# 01_MCU.net
KiCad netlist of a schematic drawn in Altium Designer
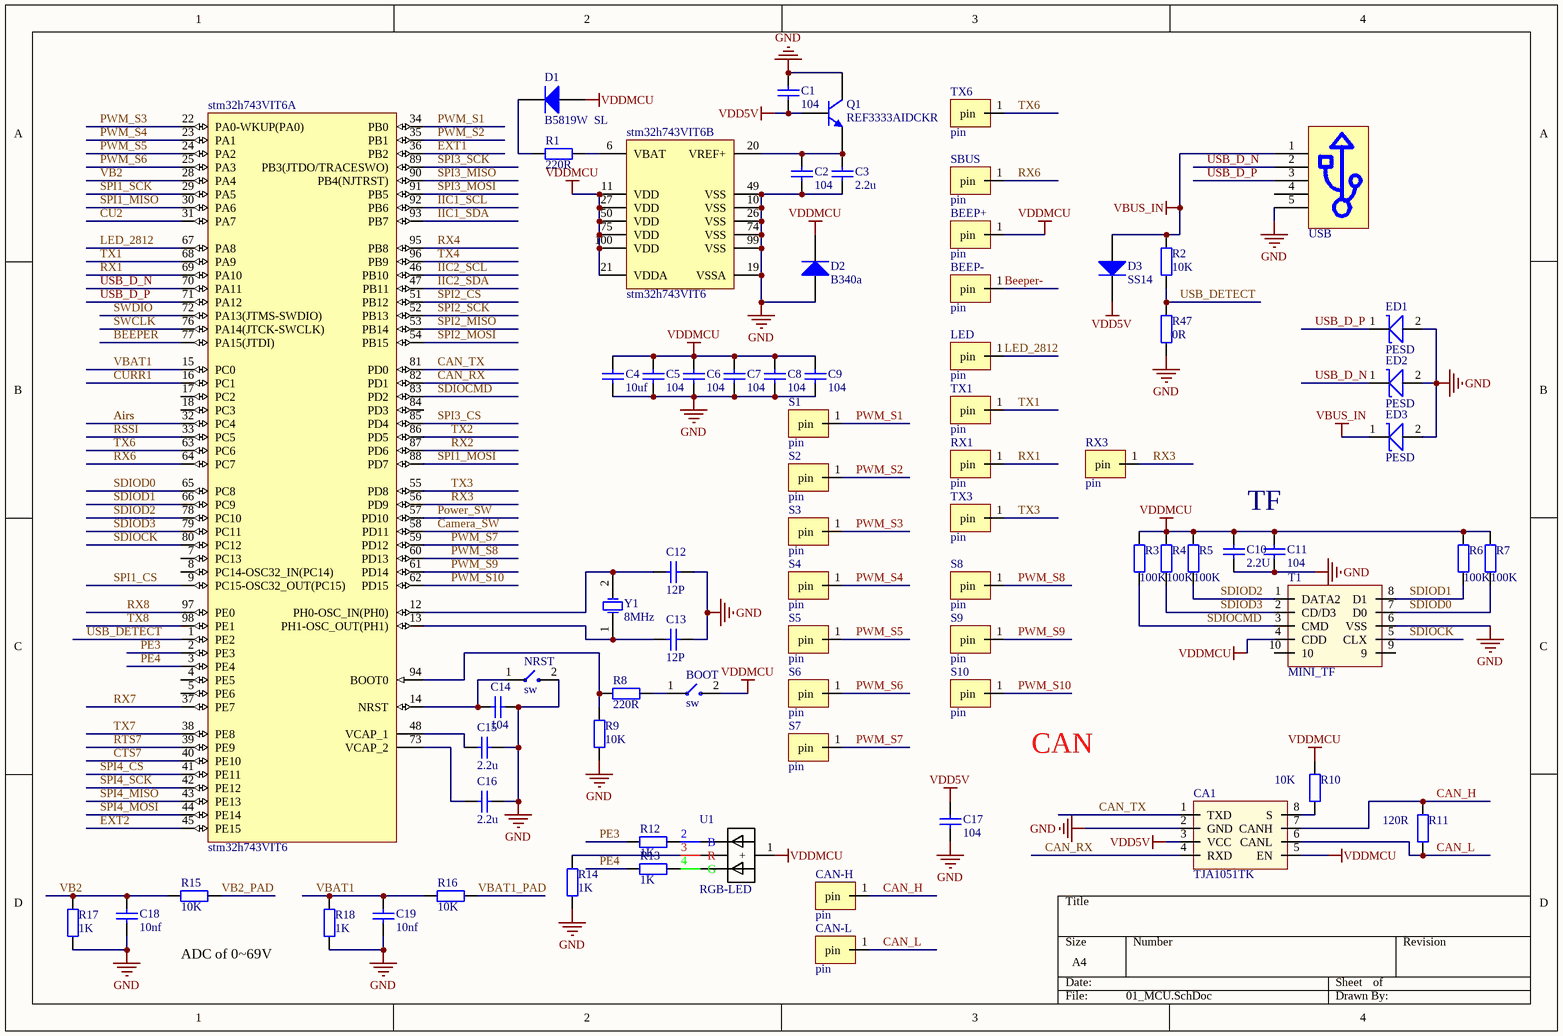
[diagram p0: 01_MCU.SchDoc]

(export (version "E")
  (design (tool "Eeschema 10.0.6"))
  (components
    (comp (ref "BEEP+") (value "pin") (footprint "DIAN_0.5-1.0") (libsource (lib "My_schlib") (part "dian")))
    (comp (ref "BEEP-") (value "pin") (footprint "DIAN_0.5-1.0") (libsource (lib "My_schlib") (part "dian")))
    (comp (ref "BOOT") (value "sw") (footprint "SW_3*4mm") (libsource (lib "My_schlib") (part "SW3*4mm")))
    (comp (ref "C1")
      (value "104")
      (footprint "0402_C")
      (description "贴片电容")
      (libsource (lib "Miscellaneous Devices LC") (part "0402 100nF (104) 10% 16V"))
    )
    (comp (ref "C2")
      (value "104")
      (footprint "0402_C")
      (description "贴片电容")
      (libsource (lib "Miscellaneous Devices LC") (part "0402 100nF (104) 10% 16V"))
    )
    (comp (ref "C3")
      (value "2.2u")
      (footprint "0603_C")
      (description "贴片电容")
      (libsource (lib "Miscellaneous Devices LC") (part "0603 10nF (103) 10% 50V"))
    )
    (comp (ref "C4")
      (value "10uf")
      (footprint "0603_C")
      (description "贴片电容")
      (libsource (lib "Miscellaneous Devices LC") (part "0603 10nF (103) 10% 50V"))
    )
    (comp (ref "C5")
      (value "104")
      (footprint "0402_C")
      (description "贴片电容")
      (libsource (lib "Miscellaneous Devices LC") (part "0402 100nF (104) 10% 16V"))
    )
    (comp (ref "C6")
      (value "104")
      (footprint "0402_C")
      (description "贴片电容")
      (libsource (lib "Miscellaneous Devices LC") (part "0402 100nF (104) 10% 16V"))
    )
    (comp (ref "C7")
      (value "104")
      (footprint "0402_C")
      (description "贴片电容")
      (libsource (lib "Miscellaneous Devices LC") (part "0402 100nF (104) 10% 16V"))
    )
    (comp (ref "C8")
      (value "104")
      (footprint "0402_C")
      (description "贴片电容")
      (libsource (lib "Miscellaneous Devices LC") (part "0402 100nF (104) 10% 16V"))
    )
    (comp (ref "C9")
      (value "104")
      (footprint "0402_C")
      (description "贴片电容")
      (libsource (lib "Miscellaneous Devices LC") (part "0402 100nF (104) 10% 16V"))
    )
    (comp (ref "C10")
      (value "2.2U")
      (footprint "0603_C")
      (description "贴片电容")
      (libsource (lib "Miscellaneous Devices LC") (part "0603 100nF (104) 10% 50V"))
    )
    (comp (ref "C11")
      (value "104")
      (footprint "0402_C")
      (description "贴片电容")
      (libsource (lib "Miscellaneous Devices LC") (part "0402 100nF (104) 10% 16V"))
    )
    (comp (ref "C12")
      (value "12P")
      (footprint "0402_C")
      (description "贴片电容")
      (libsource (lib "Miscellaneous Devices LC") (part "0402 100nF (104) 10% 16V"))
    )
    (comp (ref "C13")
      (value "12P")
      (footprint "0402_C")
      (description "贴片电容")
      (libsource (lib "Miscellaneous Devices LC") (part "0402 100nF (104) 10% 16V"))
    )
    (comp (ref "C14")
      (value "104")
      (footprint "0402_C")
      (description "贴片电容")
      (libsource (lib "Miscellaneous Devices LC") (part "0402 100nF (104) 10% 16V"))
    )
    (comp (ref "C15")
      (value "2.2u")
      (footprint "0603_C")
      (description "贴片电容")
      (libsource (lib "Miscellaneous Devices LC") (part "0603 10nF (103) 10% 50V"))
    )
    (comp (ref "C16")
      (value "2.2u")
      (footprint "0603_C")
      (description "贴片电容")
      (libsource (lib "Miscellaneous Devices LC") (part "0603 10nF (103) 10% 50V"))
    )
    (comp (ref "C17")
      (value "104")
      (footprint "0402_C")
      (description "贴片电容")
      (libsource (lib "Miscellaneous Devices LC") (part "0402 100nF (104) 10% 16V"))
    )
    (comp (ref "C18")
      (value "10nf")
      (footprint "0402_C")
      (description "贴片电容")
      (libsource (lib "Miscellaneous Devices LC") (part "0402 100nF (104) 10% 16V"))
    )
    (comp (ref "C19")
      (value "10nf")
      (footprint "0402_C")
      (description "贴片电容")
      (libsource (lib "Miscellaneous Devices LC") (part "0402 100nF (104) 10% 16V"))
    )
    (comp (ref "CA1")
      (value "TJA1051TK")
      (footprint "CAN-TJA1051TK")
      (description "CAN收发器")
      (libsource (lib "My_schlib") (part "TJA1051TK"))
    )
    (comp (ref "CAN-H") (value "pin") (footprint "DIAN_0.5-1.0") (libsource (lib "My_schlib") (part "dian")))
    (comp (ref "CAN-L") (value "pin") (footprint "DIAN_0.5-1.0") (libsource (lib "My_schlib") (part "dian")))
    (comp (ref "D1")
      (value "B5819W  SL")
      (footprint "SOD-123")
      (description "肖特基二极管")
      (libsource (lib "Miscellaneous Devices LC") (part "SOD-123 B5819W  SL"))
    )
    (comp (ref "D2")
      (value "B340a")
      (footprint "SMA(DO-214AC)_S1")
      (description "二极管")
      (libsource (lib "Miscellaneous Devices LC") (part "SMA(DO-214AC) M7"))
    )
    (comp (ref "D3")
      (value "SS14")
      (footprint "SMA(DO-214AC)_S1")
      (description "二极管")
      (libsource (lib "Miscellaneous Devices LC") (part "SMA(DO-214AC) SS54"))
    )
    (comp (ref "ED1")
      (value "PESD")
      (footprint "PESD0402")
      (description "ESD")
      (libsource (lib "My_schlib") (part "PESD0402"))
    )
    (comp (ref "ED2")
      (value "PESD")
      (footprint "PESD0402")
      (description "ESD")
      (libsource (lib "My_schlib") (part "PESD0402"))
    )
    (comp (ref "ED3")
      (value "PESD")
      (footprint "PESD0402")
      (description "ESD")
      (libsource (lib "My_schlib") (part "PESD0402"))
    )
    (comp (ref "LED") (value "pin") (footprint "DIAN_0.5-1.0") (libsource (lib "My_schlib") (part "dian")))
    (comp (ref "NRST") (value "sw") (footprint "SW_3*4mm") (libsource (lib "My_schlib") (part "SW3*4mm")))
    (comp (ref "Q1")
      (value "REF3333AIDCKR")
      (footprint "SOT-23(SOT-23-3)")
      (description "三极管")
      (libsource (lib "Miscellaneous Devices LC") (part "SOT-23 SS8050 Y1"))
    )
    (comp (ref "R1")
      (value "220R")
      (footprint "0402_R")
      (description "贴片电阻")
      (libsource (lib "") (part "0402 100Ω (1000) 1%_3"))
    )
    (comp (ref "R2")
      (value "10K")
      (footprint "0402_R")
      (description "贴片电阻")
      (libsource (lib "Miscellaneous Devices LC") (part "0402 100Ω (1000) 1%"))
    )
    (comp (ref "R3")
      (value "100K")
      (footprint "0402_R")
      (description "贴片电阻")
      (libsource (lib "Miscellaneous Devices LC") (part "0402 100Ω (1000) 1%"))
    )
    (comp (ref "R4")
      (value "100K")
      (footprint "0402_R")
      (description "贴片电阻")
      (libsource (lib "Miscellaneous Devices LC") (part "0402 100Ω (1000) 1%"))
    )
    (comp (ref "R5")
      (value "100K")
      (footprint "0402_R")
      (description "贴片电阻")
      (libsource (lib "Miscellaneous Devices LC") (part "0402 100Ω (1000) 1%"))
    )
    (comp (ref "R6")
      (value "100K")
      (footprint "0402_R")
      (description "贴片电阻")
      (libsource (lib "Miscellaneous Devices LC") (part "0402 100Ω (1000) 1%"))
    )
    (comp (ref "R7")
      (value "100K")
      (footprint "0402_R")
      (description "贴片电阻")
      (libsource (lib "Miscellaneous Devices LC") (part "0402 100Ω (1000) 1%"))
    )
    (comp (ref "R8")
      (value "220R")
      (footprint "0402_R")
      (description "贴片电阻")
      (libsource (lib "") (part "0402 100Ω (1000) 1%_3"))
    )
    (comp (ref "R9")
      (value "10K")
      (footprint "0402_R")
      (description "贴片电阻")
      (libsource (lib "Miscellaneous Devices LC") (part "0402 100Ω (1000) 1%"))
    )
    (comp (ref "R10")
      (value "10K")
      (footprint "0402_R")
      (description "贴片电阻")
      (libsource (lib "Miscellaneous Devices LC") (part "0402 100Ω (1000) 1%"))
    )
    (comp (ref "R11")
      (value "120R")
      (footprint "0402_R")
      (description "贴片电阻")
      (libsource (lib "Miscellaneous Devices LC") (part "0402 100Ω (1000) 1%"))
    )
    (comp (ref "R12")
      (value "1K")
      (footprint "0402_R")
      (description "贴片电阻")
      (libsource (lib "") (part "0402 100Ω (1000) 1%_3"))
    )
    (comp (ref "R13")
      (value "1K")
      (footprint "0402_R")
      (description "贴片电阻")
      (libsource (lib "") (part "0402 100Ω (1000) 1%_3"))
    )
    (comp (ref "R14")
      (value "1K")
      (footprint "0402_R")
      (description "贴片电阻")
      (libsource (lib "") (part "0402 100Ω (1000) 1%_2"))
    )
    (comp (ref "R15")
      (value "10K")
      (footprint "0402_R")
      (description "贴片电阻")
      (libsource (lib "") (part "0402 100Ω (1000) 1%_1"))
    )
    (comp (ref "R16")
      (value "10K")
      (footprint "0402_R")
      (description "贴片电阻")
      (libsource (lib "") (part "0402 100Ω (1000) 1%_1"))
    )
    (comp (ref "R17")
      (value "1K")
      (footprint "0402_R")
      (description "贴片电阻")
      (libsource (lib "") (part "0402 100Ω (1000) 1%_2"))
    )
    (comp (ref "R18")
      (value "1K")
      (footprint "0402_R")
      (description "贴片电阻")
      (libsource (lib "") (part "0402 100Ω (1000) 1%_2"))
    )
    (comp (ref "R47")
      (value "0R")
      (footprint "0402_R")
      (description "贴片电阻")
      (libsource (lib "Miscellaneous Devices LC") (part "0402 10KΩ (1002) 1%"))
    )
    (comp (ref "RX1") (value "pin") (footprint "DIAN_0.5-1.0") (libsource (lib "My_schlib") (part "dian")))
    (comp (ref "RX3") (value "pin") (footprint "DIAN_0.5-1.0") (libsource (lib "My_schlib") (part "dian")))
    (comp (ref "S1") (value "pin") (footprint "DIAN_0.5-1.0") (libsource (lib "My_schlib") (part "dian")))
    (comp (ref "S2") (value "pin") (footprint "DIAN_0.5-1.0") (libsource (lib "My_schlib") (part "dian")))
    (comp (ref "S3") (value "pin") (footprint "DIAN_0.5-1.0") (libsource (lib "My_schlib") (part "dian")))
    (comp (ref "S4") (value "pin") (footprint "DIAN_0.5-1.0") (libsource (lib "My_schlib") (part "dian")))
    (comp (ref "S5") (value "pin") (footprint "DIAN_0.5-1.0") (libsource (lib "My_schlib") (part "dian")))
    (comp (ref "S6") (value "pin") (footprint "DIAN_0.5-1.0") (libsource (lib "My_schlib") (part "dian")))
    (comp (ref "S7") (value "pin") (footprint "DIAN_0.5-1.0") (libsource (lib "My_schlib") (part "dian")))
    (comp (ref "S8") (value "pin") (footprint "DIAN_0.5-1.0") (libsource (lib "My_schlib") (part "dian")))
    (comp (ref "S9") (value "pin") (footprint "DIAN_0.5-1.0") (libsource (lib "My_schlib") (part "dian")))
    (comp (ref "S10") (value "pin") (footprint "DIAN_0.5-1.0") (libsource (lib "My_schlib") (part "dian")))
    (comp (ref "SBUS") (value "pin") (footprint "DIAN_0.5-1.0") (libsource (lib "My_schlib") (part "dian")))
    (comp (ref "stm32h743VIT6")
      (value "stm32h743VIT6")
      (footprint "LQFP100-14x14mm")
      (libsource (lib "My_schlib") (part "stm32h743VIT6"))
    )
    (comp (ref "T1")
      (value "MINI_TF")
      (footprint "mini_TF")
      (description "TF-card")
      (libsource (lib "My_schlib") (part "MINI_TF"))
    )
    (comp (ref "TX1") (value "pin") (footprint "DIAN_0.5-1.0") (libsource (lib "My_schlib") (part "dian")))
    (comp (ref "TX3") (value "pin") (footprint "DIAN_0.5-1.0") (libsource (lib "My_schlib") (part "dian")))
    (comp (ref "TX6") (value "pin") (footprint "DIAN_0.5-1.0") (libsource (lib "My_schlib") (part "dian")))
    (comp (ref "U1") (value "RGB-LED") (footprint "RGB-3528") (libsource (lib "My_schlib") (part "RGB-LED")))
    (comp (ref "USB") (value "miniUSB") (footprint "USB-MINI-2") (libsource (lib "接插件类") (part "miniUSB")))
    (comp (ref "Y1")
      (value "8MHz")
      (footprint "SMD-5032_2P")
      (description "贴片晶振")
      (libsource (lib "Miscellaneous Devices LC") (part "SMD-5032_2P 8MHz 20ppm 20pF"))
    )
  )
  (nets
    (net (code "1") (name "/Airs") (class "Default")
      (node (ref "stm32h743VIT6") (pin "32") (pinfunction "PC4_32") (pintype "bidirectional"))
    )
    (net (code "2") (name "/BEEPER") (class "Default")
      (node (ref "stm32h743VIT6") (pin "77") (pinfunction "PA15(JTDI)_77") (pintype "bidirectional"))
    )
    (net (code "3") (name "/Beeper-") (class "Default")
      (node (ref "BEEP-") (pin "1") (pinfunction "pin_1") (pintype "passive"))
    )
    (net (code "4") (name "/CAN_H") (class "Default")
      (node (ref "CA1") (pin "7") (pinfunction "CANH_7") (pintype "passive"))
      (node (ref "CAN-H") (pin "1") (pinfunction "pin_1") (pintype "passive"))
      (node (ref "R11") (pin "2") (pinfunction "2_2") (pintype "passive"))
    )
    (net (code "5") (name "/CAN_L") (class "Default")
      (node (ref "CA1") (pin "6") (pinfunction "CANL_6") (pintype "passive"))
      (node (ref "CAN-L") (pin "1") (pinfunction "pin_1") (pintype "passive"))
      (node (ref "R11") (pin "1") (pinfunction "1_1") (pintype "passive"))
    )
    (net (code "6") (name "/CAN_RX") (class "Default")
      (node (ref "CA1") (pin "4") (pinfunction "RXD_4") (pintype "passive"))
      (node (ref "stm32h743VIT6") (pin "82") (pinfunction "PD1_82") (pintype "bidirectional"))
    )
    (net (code "7") (name "/CAN_TX") (class "Default")
      (node (ref "CA1") (pin "1") (pinfunction "TXD_1") (pintype "passive"))
      (node (ref "stm32h743VIT6") (pin "81") (pinfunction "PD0_81") (pintype "bidirectional"))
    )
    (net (code "8") (name "/CTS7") (class "Default")
      (node (ref "stm32h743VIT6") (pin "40") (pinfunction "PE10_40") (pintype "bidirectional"))
    )
    (net (code "9") (name "/CU2") (class "Default")
      (node (ref "stm32h743VIT6") (pin "31") (pinfunction "PA7_31") (pintype "bidirectional"))
    )
    (net (code "10") (name "/CURR1") (class "Default")
      (node (ref "stm32h743VIT6") (pin "16") (pinfunction "PC1_16") (pintype "bidirectional"))
    )
    (net (code "11") (name "/Camera_SW") (class "Default")
      (node (ref "stm32h743VIT6") (pin "58") (pinfunction "PD11_58") (pintype "bidirectional"))
    )
    (net (code "12") (name "/EXT1") (class "Default")
      (node (ref "stm32h743VIT6") (pin "36") (pinfunction "PB2_36") (pintype "bidirectional"))
    )
    (net (code "13") (name "/EXT2") (class "Default")
      (node (ref "stm32h743VIT6") (pin "45") (pinfunction "PE15_45") (pintype "bidirectional"))
    )
    (net (code "14") (name "/IIC1_SCL") (class "Default")
      (node (ref "stm32h743VIT6") (pin "92") (pinfunction "PB6_92") (pintype "bidirectional"))
    )
    (net (code "15") (name "/IIC1_SDA") (class "Default")
      (node (ref "stm32h743VIT6") (pin "93") (pinfunction "PB7_93") (pintype "bidirectional"))
    )
    (net (code "16") (name "/IIC2_SCL") (class "Default")
      (node (ref "stm32h743VIT6") (pin "46") (pinfunction "PB10_46") (pintype "bidirectional"))
    )
    (net (code "17") (name "/IIC2_SDA") (class "Default")
      (node (ref "stm32h743VIT6") (pin "47") (pinfunction "PB11_47") (pintype "bidirectional"))
    )
    (net (code "18") (name "/LED_2812") (class "Default")
      (node (ref "LED") (pin "1") (pinfunction "pin_1") (pintype "passive"))
      (node (ref "stm32h743VIT6") (pin "67") (pinfunction "PA8_67") (pintype "bidirectional"))
    )
    (net (code "19") (name "/PE3") (class "Default")
      (node (ref "R12") (pin "2") (pinfunction "2_2") (pintype "passive"))
      (node (ref "stm32h743VIT6") (pin "2") (pinfunction "PE3_2") (pintype "bidirectional"))
    )
    (net (code "20") (name "/PE4") (class "Default")
      (node (ref "R13") (pin "2") (pinfunction "2_2") (pintype "passive"))
      (node (ref "stm32h743VIT6") (pin "3") (pinfunction "PE4_3") (pintype "bidirectional"))
    )
    (net (code "21") (name "/PWM_S1") (class "Default")
      (node (ref "S1") (pin "1") (pinfunction "pin_1") (pintype "passive"))
      (node (ref "stm32h743VIT6") (pin "34") (pinfunction "PB0_34") (pintype "bidirectional"))
    )
    (net (code "22") (name "/PWM_S2") (class "Default")
      (node (ref "S2") (pin "1") (pinfunction "pin_1") (pintype "passive"))
      (node (ref "stm32h743VIT6") (pin "35") (pinfunction "PB1_35") (pintype "bidirectional"))
    )
    (net (code "23") (name "/PWM_S3") (class "Default")
      (node (ref "S3") (pin "1") (pinfunction "pin_1") (pintype "passive"))
      (node (ref "stm32h743VIT6") (pin "22") (pinfunction "PA0-WKUP(PA0)_22") (pintype "bidirectional"))
    )
    (net (code "24") (name "/PWM_S4") (class "Default")
      (node (ref "S4") (pin "1") (pinfunction "pin_1") (pintype "passive"))
      (node (ref "stm32h743VIT6") (pin "23") (pinfunction "PA1_23") (pintype "bidirectional"))
    )
    (net (code "25") (name "/PWM_S5") (class "Default")
      (node (ref "S5") (pin "1") (pinfunction "pin_1") (pintype "passive"))
      (node (ref "stm32h743VIT6") (pin "24") (pinfunction "PA2_24") (pintype "bidirectional"))
    )
    (net (code "26") (name "/PWM_S6") (class "Default")
      (node (ref "S6") (pin "1") (pinfunction "pin_1") (pintype "passive"))
      (node (ref "stm32h743VIT6") (pin "25") (pinfunction "PA3_25") (pintype "bidirectional"))
    )
    (net (code "27") (name "/PWM_S7") (class "Default")
      (node (ref "S7") (pin "1") (pinfunction "pin_1") (pintype "passive"))
      (node (ref "stm32h743VIT6") (pin "59") (pinfunction "PD12_59") (pintype "bidirectional"))
    )
    (net (code "28") (name "/PWM_S8") (class "Default")
      (node (ref "S8") (pin "1") (pinfunction "pin_1") (pintype "passive"))
      (node (ref "stm32h743VIT6") (pin "60") (pinfunction "PD13_60") (pintype "bidirectional"))
    )
    (net (code "29") (name "/PWM_S9") (class "Default")
      (node (ref "S9") (pin "1") (pinfunction "pin_1") (pintype "passive"))
      (node (ref "stm32h743VIT6") (pin "61") (pinfunction "PD14_61") (pintype "bidirectional"))
    )
    (net (code "30") (name "/PWM_S10") (class "Default")
      (node (ref "S10") (pin "1") (pinfunction "pin_1") (pintype "passive"))
      (node (ref "stm32h743VIT6") (pin "62") (pinfunction "PD15_62") (pintype "bidirectional"))
    )
    (net (code "31") (name "/Power_SW") (class "Default")
      (node (ref "stm32h743VIT6") (pin "57") (pinfunction "PD10_57") (pintype "bidirectional"))
    )
    (net (code "32") (name "/RSSI") (class "Default")
      (node (ref "stm32h743VIT6") (pin "33") (pinfunction "PC5_33") (pintype "bidirectional"))
    )
    (net (code "33") (name "/RTS7") (class "Default")
      (node (ref "stm32h743VIT6") (pin "39") (pinfunction "PE9_39") (pintype "bidirectional"))
    )
    (net (code "34") (name "/RX1") (class "Default")
      (node (ref "RX1") (pin "1") (pinfunction "pin_1") (pintype "passive"))
      (node (ref "stm32h743VIT6") (pin "69") (pinfunction "PA10_69") (pintype "bidirectional"))
    )
    (net (code "35") (name "/RX2") (class "Default")
      (node (ref "stm32h743VIT6") (pin "87") (pinfunction "PD6_87") (pintype "bidirectional"))
    )
    (net (code "36") (name "/RX3") (class "Default")
      (node (ref "RX3") (pin "1") (pinfunction "pin_1") (pintype "passive"))
      (node (ref "stm32h743VIT6") (pin "56") (pinfunction "PD9_56") (pintype "bidirectional"))
    )
    (net (code "37") (name "/RX4") (class "Default")
      (node (ref "stm32h743VIT6") (pin "95") (pinfunction "PB8_95") (pintype "bidirectional"))
    )
    (net (code "38") (name "/RX6") (class "Default")
      (node (ref "SBUS") (pin "1") (pinfunction "pin_1") (pintype "passive"))
      (node (ref "stm32h743VIT6") (pin "64") (pinfunction "PC7_64") (pintype "bidirectional"))
    )
    (net (code "39") (name "/RX7") (class "Default")
      (node (ref "stm32h743VIT6") (pin "37") (pinfunction "PE7_37") (pintype "bidirectional"))
    )
    (net (code "40") (name "/RX8") (class "Default")
      (node (ref "stm32h743VIT6") (pin "97") (pinfunction "PE0_97") (pintype "bidirectional"))
    )
    (net (code "41") (name "/SDIOCK") (class "Default")
      (node (ref "T1") (pin "5") (pinfunction "CLX_5") (pintype "passive"))
      (node (ref "stm32h743VIT6") (pin "80") (pinfunction "PC12_80") (pintype "bidirectional"))
    )
    (net (code "42") (name "/SDIOCMD") (class "Default")
      (node (ref "R3") (pin "1") (pinfunction "1_1") (pintype "passive"))
      (node (ref "T1") (pin "3") (pinfunction "CMD_3") (pintype "passive"))
      (node (ref "stm32h743VIT6") (pin "83") (pinfunction "PD2_83") (pintype "bidirectional"))
    )
    (net (code "43") (name "/SDIOD0") (class "Default")
      (node (ref "R7") (pin "1") (pinfunction "1_1") (pintype "passive"))
      (node (ref "T1") (pin "7") (pinfunction "D0_7") (pintype "passive"))
      (node (ref "stm32h743VIT6") (pin "65") (pinfunction "PC8_65") (pintype "bidirectional"))
    )
    (net (code "44") (name "/SDIOD1") (class "Default")
      (node (ref "R6") (pin "1") (pinfunction "1_1") (pintype "passive"))
      (node (ref "T1") (pin "8") (pinfunction "D1_8") (pintype "passive"))
      (node (ref "stm32h743VIT6") (pin "66") (pinfunction "PC9_66") (pintype "bidirectional"))
    )
    (net (code "45") (name "/SDIOD2") (class "Default")
      (node (ref "R5") (pin "1") (pinfunction "1_1") (pintype "passive"))
      (node (ref "T1") (pin "1") (pinfunction "DATA2_1") (pintype "passive"))
      (node (ref "stm32h743VIT6") (pin "78") (pinfunction "PC10_78") (pintype "bidirectional"))
    )
    (net (code "46") (name "/SDIOD3") (class "Default")
      (node (ref "R4") (pin "1") (pinfunction "1_1") (pintype "passive"))
      (node (ref "T1") (pin "2") (pinfunction "CD/D3_2") (pintype "passive"))
      (node (ref "stm32h743VIT6") (pin "79") (pinfunction "PC11_79") (pintype "bidirectional"))
    )
    (net (code "47") (name "/SPI1_CS") (class "Default")
      (node (ref "stm32h743VIT6") (pin "9") (pinfunction "PC15-OSC32_OUT(PC15)_9") (pintype "bidirectional"))
    )
    (net (code "48") (name "/SPI1_MISO") (class "Default")
      (node (ref "stm32h743VIT6") (pin "30") (pinfunction "PA6_30") (pintype "bidirectional"))
    )
    (net (code "49") (name "/SPI1_MOSI") (class "Default")
      (node (ref "stm32h743VIT6") (pin "88") (pinfunction "PD7_88") (pintype "bidirectional"))
    )
    (net (code "50") (name "/SPI1_SCK") (class "Default")
      (node (ref "stm32h743VIT6") (pin "29") (pinfunction "PA5_29") (pintype "bidirectional"))
    )
    (net (code "51") (name "/SPI2_CS") (class "Default")
      (node (ref "stm32h743VIT6") (pin "51") (pinfunction "PB12_51") (pintype "bidirectional"))
    )
    (net (code "52") (name "/SPI2_MISO") (class "Default")
      (node (ref "stm32h743VIT6") (pin "53") (pinfunction "PB14_53") (pintype "bidirectional"))
    )
    (net (code "53") (name "/SPI2_MOSI") (class "Default")
      (node (ref "stm32h743VIT6") (pin "54") (pinfunction "PB15_54") (pintype "bidirectional"))
    )
    (net (code "54") (name "/SPI2_SCK") (class "Default")
      (node (ref "stm32h743VIT6") (pin "52") (pinfunction "PB13_52") (pintype "bidirectional"))
    )
    (net (code "55") (name "/SPI3_CS") (class "Default")
      (node (ref "stm32h743VIT6") (pin "85") (pinfunction "PD4_85") (pintype "bidirectional"))
    )
    (net (code "56") (name "/SPI3_MISO") (class "Default")
      (node (ref "stm32h743VIT6") (pin "90") (pinfunction "PB4(NJTRST)_90") (pintype "bidirectional"))
    )
    (net (code "57") (name "/SPI3_MOSI") (class "Default")
      (node (ref "stm32h743VIT6") (pin "91") (pinfunction "PB5_91") (pintype "bidirectional"))
    )
    (net (code "58") (name "/SPI3_SCK") (class "Default")
      (node (ref "stm32h743VIT6") (pin "89") (pinfunction "PB3(JTDO/TRACESWO)_89") (pintype "bidirectional"))
    )
    (net (code "59") (name "/SPI4_CS") (class "Default")
      (node (ref "stm32h743VIT6") (pin "41") (pinfunction "PE11_41") (pintype "bidirectional"))
    )
    (net (code "60") (name "/SPI4_MISO") (class "Default")
      (node (ref "stm32h743VIT6") (pin "43") (pinfunction "PE13_43") (pintype "bidirectional"))
    )
    (net (code "61") (name "/SPI4_MOSI") (class "Default")
      (node (ref "stm32h743VIT6") (pin "44") (pinfunction "PE14_44") (pintype "bidirectional"))
    )
    (net (code "62") (name "/SPI4_SCK") (class "Default")
      (node (ref "stm32h743VIT6") (pin "42") (pinfunction "PE12_42") (pintype "bidirectional"))
    )
    (net (code "63") (name "/SWCLK") (class "Default")
      (node (ref "stm32h743VIT6") (pin "76") (pinfunction "PA14(JTCK-SWCLK)_76") (pintype "bidirectional"))
    )
    (net (code "64") (name "/SWDIO") (class "Default")
      (node (ref "stm32h743VIT6") (pin "72") (pinfunction "PA13(JTMS-SWDIO)_72") (pintype "bidirectional"))
    )
    (net (code "65") (name "/TX1") (class "Default")
      (node (ref "TX1") (pin "1") (pinfunction "pin_1") (pintype "passive"))
      (node (ref "stm32h743VIT6") (pin "68") (pinfunction "PA9_68") (pintype "bidirectional"))
    )
    (net (code "66") (name "/TX2") (class "Default")
      (node (ref "stm32h743VIT6") (pin "86") (pinfunction "PD5_86") (pintype "bidirectional"))
    )
    (net (code "67") (name "/TX3") (class "Default")
      (node (ref "TX3") (pin "1") (pinfunction "pin_1") (pintype "passive"))
      (node (ref "stm32h743VIT6") (pin "55") (pinfunction "PD8_55") (pintype "bidirectional"))
    )
    (net (code "68") (name "/TX4") (class "Default")
      (node (ref "stm32h743VIT6") (pin "96") (pinfunction "PB9_96") (pintype "bidirectional"))
    )
    (net (code "69") (name "/TX6") (class "Default")
      (node (ref "TX6") (pin "1") (pinfunction "pin_1") (pintype "passive"))
      (node (ref "stm32h743VIT6") (pin "63") (pinfunction "PC6_63") (pintype "bidirectional"))
    )
    (net (code "70") (name "/TX7") (class "Default")
      (node (ref "stm32h743VIT6") (pin "38") (pinfunction "PE8_38") (pintype "bidirectional"))
    )
    (net (code "71") (name "/TX8") (class "Default")
      (node (ref "stm32h743VIT6") (pin "98") (pinfunction "PE1_98") (pintype "bidirectional"))
    )
    (net (code "72") (name "/USB_DETECT") (class "Default")
      (node (ref "R2") (pin "1") (pinfunction "1_1") (pintype "passive"))
      (node (ref "R47") (pin "1") (pinfunction "1_1") (pintype "passive"))
      (node (ref "stm32h743VIT6") (pin "1") (pinfunction "PE2_1") (pintype "bidirectional"))
    )
    (net (code "73") (name "/USB_D_N") (class "Default")
      (node (ref "ED2") (pin "1") (pintype "passive"))
      (node (ref "USB") (pin "2") (pinfunction "2_2") (pintype "passive"))
      (node (ref "stm32h743VIT6") (pin "70") (pinfunction "PA11_70") (pintype "bidirectional"))
    )
    (net (code "74") (name "/USB_D_P") (class "Default")
      (node (ref "ED1") (pin "1") (pintype "passive"))
      (node (ref "USB") (pin "3") (pinfunction "3_3") (pintype "passive"))
      (node (ref "stm32h743VIT6") (pin "71") (pinfunction "PA12_71") (pintype "bidirectional"))
    )
    (net (code "75") (name "/VB2") (class "Default")
      (node (ref "C18") (pin "2") (pinfunction "2_2") (pintype "passive"))
      (node (ref "R15") (pin "1") (pinfunction "1_1") (pintype "passive"))
      (node (ref "R17") (pin "1") (pinfunction "1_1") (pintype "passive"))
      (node (ref "stm32h743VIT6") (pin "28") (pinfunction "PA4_28") (pintype "bidirectional"))
    )
    (net (code "76") (name "/VB2_PAD") (class "Default")
      (node (ref "R15") (pin "2") (pinfunction "2_2") (pintype "passive"))
    )
    (net (code "77") (name "/VBAT1") (class "Default")
      (node (ref "C19") (pin "2") (pinfunction "2_2") (pintype "passive"))
      (node (ref "R16") (pin "1") (pinfunction "1_1") (pintype "passive"))
      (node (ref "R18") (pin "1") (pinfunction "1_1") (pintype "passive"))
      (node (ref "stm32h743VIT6") (pin "15") (pinfunction "PC0_15") (pintype "bidirectional"))
    )
    (net (code "78") (name "/VBAT1_PAD") (class "Default")
      (node (ref "R16") (pin "2") (pinfunction "2_2") (pintype "passive"))
    )
    (net (code "79") (name "GND") (class "Default")
      (node (ref "C1") (pin "1") (pinfunction "1_1") (pintype "passive"))
      (node (ref "C10") (pin "1") (pinfunction "1_1") (pintype "passive"))
      (node (ref "C11") (pin "1") (pinfunction "1_1") (pintype "passive"))
      (node (ref "C12") (pin "1") (pinfunction "1_1") (pintype "passive"))
      (node (ref "C13") (pin "1") (pinfunction "1_1") (pintype "passive"))
      (node (ref "C14") (pin "1") (pinfunction "1_1") (pintype "passive"))
      (node (ref "C15") (pin "1") (pinfunction "1_1") (pintype "passive"))
      (node (ref "C16") (pin "1") (pinfunction "1_1") (pintype "passive"))
      (node (ref "C17") (pin "2") (pinfunction "2_2") (pintype "passive"))
      (node (ref "C18") (pin "1") (pinfunction "1_1") (pintype "passive"))
      (node (ref "C19") (pin "1") (pinfunction "1_1") (pintype "passive"))
      (node (ref "C2") (pin "1") (pinfunction "1_1") (pintype "passive"))
      (node (ref "C3") (pin "1") (pinfunction "1_1") (pintype "passive"))
      (node (ref "C4") (pin "1") (pinfunction "1_1") (pintype "passive"))
      (node (ref "C5") (pin "2") (pinfunction "2_2") (pintype "passive"))
      (node (ref "C6") (pin "2") (pinfunction "2_2") (pintype "passive"))
      (node (ref "C7") (pin "2") (pinfunction "2_2") (pintype "passive"))
      (node (ref "C8") (pin "2") (pinfunction "2_2") (pintype "passive"))
      (node (ref "C9") (pin "2") (pinfunction "2_2") (pintype "passive"))
      (node (ref "CA1") (pin "2") (pinfunction "GND_2") (pintype "passive"))
      (node (ref "D2") (pin "1") (pinfunction "A_1") (pintype "passive"))
      (node (ref "ED1") (pin "2") (pintype "passive"))
      (node (ref "ED2") (pin "2") (pintype "passive"))
      (node (ref "ED3") (pin "2") (pintype "passive"))
      (node (ref "NRST") (pin "2") (pinfunction "2_2") (pintype "passive"))
      (node (ref "Q1") (pin "3") (pinfunction "C_3") (pintype "passive"))
      (node (ref "R14") (pin "2") (pinfunction "2_2") (pintype "passive"))
      (node (ref "R17") (pin "2") (pinfunction "2_2") (pintype "passive"))
      (node (ref "R18") (pin "2") (pinfunction "2_2") (pintype "passive"))
      (node (ref "R47") (pin "2") (pinfunction "2_2") (pintype "passive"))
      (node (ref "R9") (pin "1") (pinfunction "1_1") (pintype "passive"))
      (node (ref "T1") (pin "6") (pinfunction "VSS_6") (pintype "passive"))
      (node (ref "USB") (pin "5") (pinfunction "5_5") (pintype "passive"))
      (node (ref "stm32h743VIT6") (pin "10") (pinfunction "VSS_10") (pintype "power_in"))
      (node (ref "stm32h743VIT6") (pin "19") (pinfunction "VSSA_19") (pintype "power_in"))
      (node (ref "stm32h743VIT6") (pin "26") (pinfunction "VSS_26") (pintype "power_in"))
      (node (ref "stm32h743VIT6") (pin "49") (pinfunction "VSS_49") (pintype "power_in"))
      (node (ref "stm32h743VIT6") (pin "74") (pinfunction "VSS_74") (pintype "power_in"))
      (node (ref "stm32h743VIT6") (pin "99") (pinfunction "VSS_99") (pintype "power_in"))
    )
    (net (code "80") (name "Net-(BOOT-Pad1)") (class "Default")
      (node (ref "BOOT") (pin "1") (pinfunction "1_1") (pintype "passive"))
      (node (ref "R8") (pin "1") (pinfunction "1_1") (pintype "passive"))
    )
    (net (code "81") (name "Net-(CA1-S)") (class "Default")
      (node (ref "CA1") (pin "8") (pinfunction "S_8") (pintype "passive"))
      (node (ref "R10") (pin "1") (pinfunction "1_1") (pintype "passive"))
    )
    (net (code "82") (name "Net-(D1-K)") (class "Default")
      (node (ref "D1") (pin "2") (pinfunction "K_2") (pintype "passive"))
      (node (ref "R1") (pin "2") (pinfunction "2_2") (pintype "passive"))
    )
    (net (code "83") (name "Net-(Q1-E)") (class "Default")
      (node (ref "C2") (pin "2") (pinfunction "2_2") (pintype "passive"))
      (node (ref "C3") (pin "2") (pinfunction "2_2") (pintype "passive"))
      (node (ref "Q1") (pin "2") (pinfunction "E_2") (pintype "passive"))
      (node (ref "stm32h743VIT6") (pin "20") (pinfunction "VREF+_20") (pintype "power_in"))
    )
    (net (code "84") (name "Net-(U1-B)") (class "Default")
      (node (ref "R12") (pin "1") (pinfunction "1_1") (pintype "passive"))
      (node (ref "U1") (pin "2") (pinfunction "B_2") (pintype "passive"))
    )
    (net (code "85") (name "Net-(U1-G)") (class "Default")
      (node (ref "R13") (pin "1") (pinfunction "1_1") (pintype "passive"))
      (node (ref "U1") (pin "4") (pinfunction "G_4") (pintype "passive"))
    )
    (net (code "86") (name "Net-(U1-R)") (class "Default")
      (node (ref "R14") (pin "1") (pinfunction "1_1") (pintype "passive"))
      (node (ref "U1") (pin "3") (pinfunction "R_3") (pintype "passive"))
    )
    (net (code "87") (name "Net-(Y1-OSC1)") (class "Default")
      (node (ref "C13") (pin "2") (pinfunction "2_2") (pintype "passive"))
      (node (ref "Y1") (pin "1") (pinfunction "OSC1_1") (pintype "passive"))
      (node (ref "stm32h743VIT6") (pin "13") (pinfunction "PH1-OSC_OUT(PH1)_13") (pintype "bidirectional"))
    )
    (net (code "88") (name "Net-(Y1-OSC2)") (class "Default")
      (node (ref "C12") (pin "2") (pinfunction "2_2") (pintype "passive"))
      (node (ref "Y1") (pin "2") (pinfunction "OSC2_2") (pintype "passive"))
      (node (ref "stm32h743VIT6") (pin "12") (pinfunction "PH0-OSC_IN(PH0)_12") (pintype "bidirectional"))
    )
    (net (code "89") (name "Net-(stm32h743VIT6A-BOOT0)") (class "Default")
      (node (ref "R8") (pin "2") (pinfunction "2_2") (pintype "passive"))
      (node (ref "R9") (pin "2") (pinfunction "2_2") (pintype "passive"))
      (node (ref "stm32h743VIT6") (pin "94") (pinfunction "BOOT0_94") (pintype "input"))
    )
    (net (code "90") (name "Net-(stm32h743VIT6A-NRST)") (class "Default")
      (node (ref "C14") (pin "2") (pinfunction "2_2") (pintype "passive"))
      (node (ref "NRST") (pin "1") (pinfunction "1_1") (pintype "passive"))
      (node (ref "stm32h743VIT6") (pin "14") (pinfunction "NRST_14") (pintype "bidirectional"))
    )
    (net (code "91") (name "Net-(stm32h743VIT6A-VCAP_1)") (class "Default")
      (node (ref "C15") (pin "2") (pinfunction "2_2") (pintype "passive"))
      (node (ref "stm32h743VIT6") (pin "48") (pinfunction "VCAP_1_48") (pintype "power_in"))
    )
    (net (code "92") (name "Net-(stm32h743VIT6A-VCAP_2)") (class "Default")
      (node (ref "C16") (pin "2") (pinfunction "2_2") (pintype "passive"))
      (node (ref "stm32h743VIT6") (pin "73") (pinfunction "VCAP_2_73") (pintype "power_in"))
    )
    (net (code "93") (name "Net-(stm32h743VIT6B-VBAT)") (class "Default")
      (node (ref "R1") (pin "1") (pinfunction "1_1") (pintype "passive"))
      (node (ref "stm32h743VIT6") (pin "6") (pinfunction "VBAT_6") (pintype "power_in"))
    )
    (net (code "94") (name "VBUS_IN") (class "Default")
      (node (ref "D3") (pin "1") (pinfunction "A_1") (pintype "passive"))
      (node (ref "ED3") (pin "1") (pintype "passive"))
      (node (ref "R2") (pin "2") (pinfunction "2_2") (pintype "passive"))
      (node (ref "USB") (pin "1") (pinfunction "1_1") (pintype "passive"))
    )
    (net (code "95") (name "VDD5V") (class "Default")
      (node (ref "C1") (pin "2") (pinfunction "2_2") (pintype "passive"))
      (node (ref "C17") (pin "1") (pinfunction "1_1") (pintype "passive"))
      (node (ref "CA1") (pin "3") (pinfunction "VCC_3") (pintype "passive"))
      (node (ref "D3") (pin "2") (pinfunction "K_2") (pintype "passive"))
      (node (ref "Q1") (pin "1") (pinfunction "B_1") (pintype "passive"))
    )
    (net (code "96") (name "VDDMCU") (class "Default")
      (node (ref "BEEP+") (pin "1") (pinfunction "pin_1") (pintype "passive"))
      (node (ref "BOOT") (pin "2") (pinfunction "2_2") (pintype "passive"))
      (node (ref "C10") (pin "2") (pinfunction "2_2") (pintype "passive"))
      (node (ref "C11") (pin "2") (pinfunction "2_2") (pintype "passive"))
      (node (ref "C4") (pin "2") (pinfunction "2_2") (pintype "passive"))
      (node (ref "C5") (pin "1") (pinfunction "1_1") (pintype "passive"))
      (node (ref "C6") (pin "1") (pinfunction "1_1") (pintype "passive"))
      (node (ref "C7") (pin "1") (pinfunction "1_1") (pintype "passive"))
      (node (ref "C8") (pin "1") (pinfunction "1_1") (pintype "passive"))
      (node (ref "C9") (pin "1") (pinfunction "1_1") (pintype "passive"))
      (node (ref "CA1") (pin "5") (pinfunction "EN_5") (pintype "passive"))
      (node (ref "D1") (pin "1") (pinfunction "A_1") (pintype "passive"))
      (node (ref "D2") (pin "2") (pinfunction "K_2") (pintype "passive"))
      (node (ref "R10") (pin "2") (pinfunction "2_2") (pintype "passive"))
      (node (ref "R3") (pin "2") (pinfunction "2_2") (pintype "passive"))
      (node (ref "R4") (pin "2") (pinfunction "2_2") (pintype "passive"))
      (node (ref "R5") (pin "2") (pinfunction "2_2") (pintype "passive"))
      (node (ref "R6") (pin "2") (pinfunction "2_2") (pintype "passive"))
      (node (ref "R7") (pin "2") (pinfunction "2_2") (pintype "passive"))
      (node (ref "T1") (pin "4") (pinfunction "CDD_4") (pintype "passive"))
      (node (ref "U1") (pin "1") (pinfunction "+_1") (pintype "passive"))
      (node (ref "stm32h743VIT6") (pin "100") (pinfunction "VDD_100") (pintype "power_in"))
      (node (ref "stm32h743VIT6") (pin "11") (pinfunction "VDD_11") (pintype "power_in"))
      (node (ref "stm32h743VIT6") (pin "21") (pinfunction "VDDA_21") (pintype "power_in"))
      (node (ref "stm32h743VIT6") (pin "27") (pinfunction "VDD_27") (pintype "power_in"))
      (node (ref "stm32h743VIT6") (pin "50") (pinfunction "VDD_50") (pintype "power_in"))
      (node (ref "stm32h743VIT6") (pin "75") (pinfunction "VDD_75") (pintype "power_in"))
    )
    (net (code "97") (name "unconnected-(T1-Pad9)") (class "Default")
      (node (ref "T1") (pin "9") (pinfunction "9_9") (pintype "passive"))
    )
    (net (code "98") (name "unconnected-(T1-Pad10)") (class "Default")
      (node (ref "T1") (pin "10") (pinfunction "10_10") (pintype "passive"))
    )
    (net (code "99") (name "unconnected-(USB-Pad4)") (class "Default")
      (node (ref "USB") (pin "4") (pinfunction "4_4") (pintype "passive"))
    )
    (net (code "100") (name "unconnected-(stm32h743VIT6A-PC2-Pad17)") (class "Default")
      (node (ref "stm32h743VIT6") (pin "17") (pinfunction "PC2_17") (pintype "bidirectional"))
    )
    (net (code "101") (name "unconnected-(stm32h743VIT6A-PC3-Pad18)") (class "Default")
      (node (ref "stm32h743VIT6") (pin "18") (pinfunction "PC3_18") (pintype "bidirectional"))
    )
    (net (code "102") (name "unconnected-(stm32h743VIT6A-PC13-Pad7)") (class "Default")
      (node (ref "stm32h743VIT6") (pin "7") (pinfunction "PC13_7") (pintype "bidirectional"))
    )
    (net (code "103") (name "unconnected-(stm32h743VIT6A-PC14-OSC32_IN(PC14)-Pad8)") (class "Default")
      (node (ref "stm32h743VIT6") (pin "8") (pinfunction "PC14-OSC32_IN(PC14)_8") (pintype "bidirectional"))
    )
    (net (code "104") (name "unconnected-(stm32h743VIT6A-PD3-Pad84)") (class "Default")
      (node (ref "stm32h743VIT6") (pin "84") (pinfunction "PD3_84") (pintype "bidirectional"))
    )
    (net (code "105") (name "unconnected-(stm32h743VIT6A-PE5-Pad4)") (class "Default")
      (node (ref "stm32h743VIT6") (pin "4") (pinfunction "PE5_4") (pintype "bidirectional"))
    )
    (net (code "106") (name "unconnected-(stm32h743VIT6A-PE6-Pad5)") (class "Default")
      (node (ref "stm32h743VIT6") (pin "5") (pinfunction "PE6_5") (pintype "bidirectional"))
    )
  )
)
